# STM32405RG.net
KiCad netlist of a schematic drawn in Altium Designer
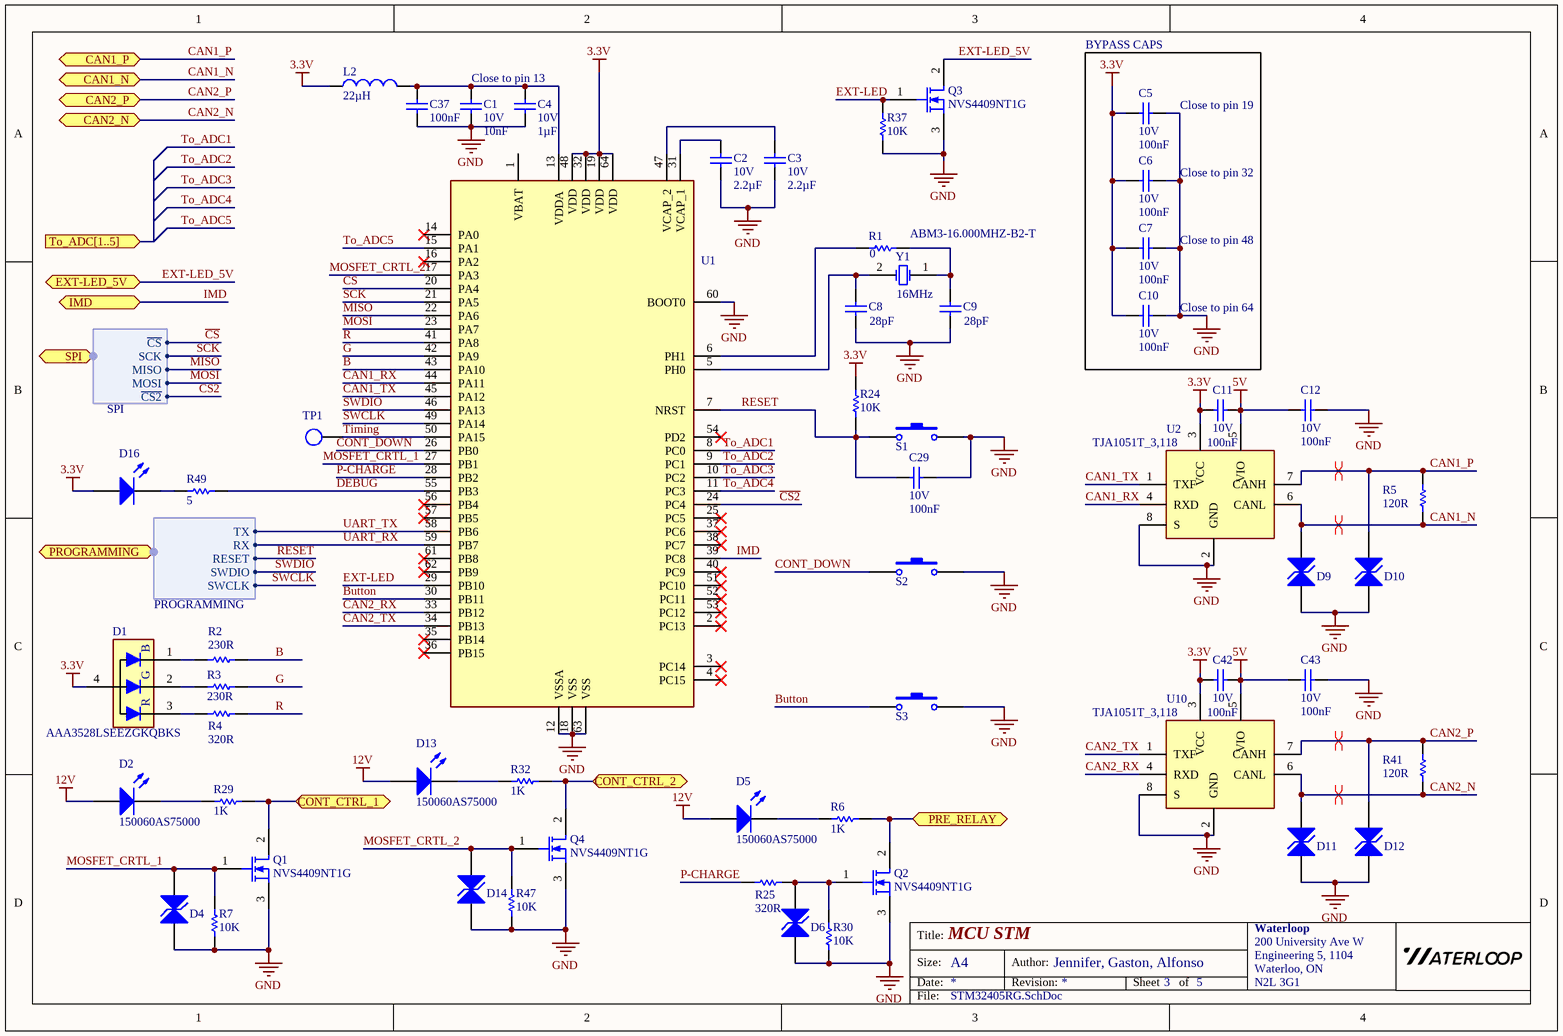
[diagram p0: STM32405RG.SchDoc]

(export (version "E")
  (design (tool "Eeschema 10.0.6"))
  (components
    (comp (ref "C1")
      (value "10V")
      (footprint "0805 - Capacitor")
      (description "C0805C103K8RAC7800. 10000pF ±10% 10V Ceramic Capacitor X7R 0805 (2012 Metric)")
      (fields (field (name "ALTIUM_VALUE") "10nF"))
      (libsource (lib "General") (part "Capacitor - Nonpolarized"))
    )
    (comp (ref "C2")
      (value "10V")
      (footprint "0805 - Capacitor")
      (description "CC0805KKX7R9BB225. 2.2µF ±10% 50V Ceramic Capacitor X7R 0805 (2012 Metric)")
      (fields (field (name "ALTIUM_VALUE") "2.2µF"))
      (libsource (lib "General") (part "Capacitor - Nonpolarized"))
    )
    (comp (ref "C3")
      (value "10V")
      (footprint "0805 - Capacitor")
      (description "CC0805KKX7R9BB225. 2.2µF ±10% 50V Ceramic Capacitor X7R 0805 (2012 Metric)")
      (fields (field (name "ALTIUM_VALUE") "2.2µF"))
      (libsource (lib "General") (part "Capacitor - Nonpolarized"))
    )
    (comp (ref "C4")
      (value "10V")
      (footprint "0805 - Capacitor")
      (description "CL21B105KPFNNNE. 1µF ±10% 10V Ceramic Capacitor X7R 0805 (2012 Metric)")
      (fields (field (name "ALTIUM_VALUE") "1µF"))
      (libsource (lib "General") (part "Capacitor - Nonpolarized"))
    )
    (comp (ref "C5")
      (value "10V")
      (footprint "0805 - Capacitor")
      (description "C0805C104K8RACTU. 0.1µF ±10% 10V Ceramic Capacitor X7R 0805 (2012 Metric)")
      (fields (field (name "ALTIUM_VALUE") "100nF"))
      (libsource (lib "General") (part "Capacitor - Nonpolarized"))
    )
    (comp (ref "C6")
      (value "10V")
      (footprint "0805 - Capacitor")
      (description "C0805C104K8RACTU. 0.1µF ±10% 10V Ceramic Capacitor X7R 0805 (2012 Metric)")
      (fields (field (name "ALTIUM_VALUE") "100nF"))
      (libsource (lib "General") (part "Capacitor - Nonpolarized"))
    )
    (comp (ref "C7")
      (value "10V")
      (footprint "0805 - Capacitor")
      (description "C0805C104K8RACTU. 0.1µF ±10% 10V Ceramic Capacitor X7R 0805 (2012 Metric)")
      (fields (field (name "ALTIUM_VALUE") "100nF"))
      (libsource (lib "General") (part "Capacitor - Nonpolarized"))
    )
    (comp (ref "C8")
      (value "28pF")
      (footprint "0805 - Capacitor")
      (description "CBR08C409B5GAC. 4pF ±0.1pF 50V Ceramic Capacitor C0G, NP0 0805 (2012 Metric)")
      (fields (field (name "Comment") "50V"))
      (libsource (lib "General") (part "Capacitor - Nonpolarized"))
    )
    (comp (ref "C9")
      (value "28pF")
      (footprint "0805 - Capacitor")
      (description "CBR08C409B5GAC. 4pF ±0.1pF 50V Ceramic Capacitor C0G, NP0 0805 (2012 Metric)")
      (fields (field (name "Comment") "50V"))
      (libsource (lib "General") (part "Capacitor - Nonpolarized"))
    )
    (comp (ref "C10")
      (value "10V")
      (footprint "0805 - Capacitor")
      (description "C0805C104K8RACTU. 0.1µF ±10% 10V Ceramic Capacitor X7R 0805 (2012 Metric)")
      (fields (field (name "ALTIUM_VALUE") "100nF"))
      (libsource (lib "General") (part "Capacitor - Nonpolarized"))
    )
    (comp (ref "C11")
      (value "10V")
      (footprint "0805 - Capacitor")
      (description "C0805C104K8RACTU. 0.1µF ±10% 10V Ceramic Capacitor X7R 0805 (2012 Metric)")
      (fields (field (name "ALTIUM_VALUE") "100nF"))
      (libsource (lib "") (part "Capacitor - Nonpolarized_1"))
    )
    (comp (ref "C12")
      (value "10V")
      (footprint "0805 - Capacitor")
      (description "C0805C104K8RACTU. 0.1µF ±10% 10V Ceramic Capacitor X7R 0805 (2012 Metric)")
      (fields (field (name "ALTIUM_VALUE") "100nF"))
      (libsource (lib "General") (part "Capacitor - Nonpolarized"))
    )
    (comp (ref "C29")
      (value "10V")
      (footprint "0805 - Capacitor")
      (description "C0805C104K8RACTU. 0.1µF ±10% 10V Ceramic Capacitor X7R 0805 (2012 Metric)")
      (fields (field (name "ALTIUM_VALUE") "100nF"))
      (libsource (lib "General") (part "Capacitor - Nonpolarized"))
    )
    (comp (ref "C37")
      (value "100nF")
      (footprint "0805 - Capacitor")
      (description "C0805C104K8RACTU. 0.1µF ±10% 10V Ceramic Capacitor X7R 0805 (2012 Metric)")
      (fields (field (name "Comment") "Capacitor - Nonpolarized"))
      (libsource (lib "General") (part "Capacitor - Nonpolarized"))
    )
    (comp (ref "C42")
      (value "10V")
      (footprint "0805 - Capacitor")
      (description "C0805C104K8RACTU. 0.1µF ±10% 10V Ceramic Capacitor X7R 0805 (2012 Metric)")
      (fields (field (name "ALTIUM_VALUE") "100nF"))
      (libsource (lib "") (part "Capacitor - Nonpolarized_1"))
    )
    (comp (ref "C43")
      (value "10V")
      (footprint "0805 - Capacitor")
      (description "C0805C104K8RACTU. 0.1µF ±10% 10V Ceramic Capacitor X7R 0805 (2012 Metric)")
      (fields (field (name "ALTIUM_VALUE") "100nF"))
      (libsource (lib "General") (part "Capacitor - Nonpolarized"))
    )
    (comp (ref "D1")
      (value "AAA3528LSEEZGKQBKS")
      (footprint "4-PLCC RGB LED")
      (libsource (lib "General") (part "RGB LED- Common Anode"))
    )
    (comp (ref "D2")
      (value "150060AS75000")
      (footprint "0603 - Resistor")
      (description "Amber 605nm LED Indication - Discrete 2V 0603 (1608 Metric)")
      (libsource (lib "General") (part "LED"))
    )
    (comp (ref "D4")
      (value "TVS")
      (footprint "SOD123 - DIODE")
      (description "TV02W5V0B-G, TVS DIODE 5VWM 9.2VC SOD123")
      (libsource (lib "General") (part "TVS"))
    )
    (comp (ref "D5")
      (value "150060AS75000")
      (footprint "0603 - Resistor")
      (description "Amber 605nm LED Indication - Discrete 2V 0603 (1608 Metric)")
      (libsource (lib "General") (part "LED"))
    )
    (comp (ref "D6")
      (value "TVS")
      (footprint "SOD123 - DIODE")
      (description "TV02W5V0B-G, TVS DIODE 5VWM 9.2VC SOD123")
      (libsource (lib "General") (part "TVS"))
    )
    (comp (ref "D9")
      (value "TVS")
      (footprint "SOD123 - DIODE")
      (description "TV02W5V0B-G, TVS DIODE 5VWM 9.2VC SOD123")
      (libsource (lib "General") (part "TVS"))
    )
    (comp (ref "D10")
      (value "TVS")
      (footprint "SOD123 - DIODE")
      (description "TV02W5V0B-G, TVS DIODE 5VWM 9.2VC SOD123")
      (libsource (lib "General") (part "TVS"))
    )
    (comp (ref "D11")
      (value "TVS")
      (footprint "SOD123 - DIODE")
      (description "TV02W5V0B-G, TVS DIODE 5VWM 9.2VC SOD123")
      (libsource (lib "General") (part "TVS"))
    )
    (comp (ref "D12")
      (value "TVS")
      (footprint "SOD123 - DIODE")
      (description "TV02W5V0B-G, TVS DIODE 5VWM 9.2VC SOD123")
      (libsource (lib "General") (part "TVS"))
    )
    (comp (ref "D13")
      (value "150060AS75000")
      (footprint "0603 - Resistor")
      (description "Amber 605nm LED Indication - Discrete 2V 0603 (1608 Metric)")
      (libsource (lib "General") (part "LED"))
    )
    (comp (ref "D14")
      (value "TVS")
      (footprint "SOD123 - DIODE")
      (description "TV02W5V0B-G, TVS DIODE 5VWM 9.2VC SOD123")
      (libsource (lib "General") (part "TVS"))
    )
    (comp (ref "D16")
      (value "LED")
      (footprint "0805 - Resistor")
      (description "150080BS75000, LED BLUE CLEAR 0805 SMD")
      (libsource (lib "General") (part "LED"))
    )
    (comp (ref "L2")
      (value "22µH")
      (footprint "0805 - Capacitor")
      (description "LBR2012T220K, 22 µH ±10% 100 mA 0805 (2012 Metric)")
      (fields (field (name "Comment") "Inductor"))
      (libsource (lib "General") (part "Inductor"))
    )
    (comp (ref "Q1")
      (value "NVS4409NT1G")
      (footprint "SC70/SOT323")
      (description "N-Channel MOSFET")
      (libsource (lib "General") (part "MOSFET-N"))
    )
    (comp (ref "Q2")
      (value "NVS4409NT1G")
      (footprint "SC70/SOT323")
      (description "N-Channel MOSFET")
      (libsource (lib "General") (part "MOSFET-N"))
    )
    (comp (ref "Q3")
      (value "NVS4409NT1G")
      (footprint "SC70/SOT323")
      (description "N-Channel MOSFET")
      (libsource (lib "General") (part "MOSFET-N"))
    )
    (comp (ref "Q4")
      (value "NVS4409NT1G")
      (footprint "SC70/SOT323")
      (description "N-Channel MOSFET")
      (libsource (lib "General") (part "MOSFET-N"))
    )
    (comp (ref "R1")
      (value "0")
      (footprint "0603 - Resistor")
      (fields (field (name "Comment") "0603"))
      (libsource (lib "General") (part "Resistor"))
    )
    (comp (ref "R2")
      (value "230R")
      (footprint "0603 - Resistor")
      (fields (field (name "Comment") "1%"))
      (libsource (lib "General") (part "Resistor"))
    )
    (comp (ref "R3")
      (value "230R")
      (footprint "0603 - Resistor")
      (fields (field (name "Comment") "1%"))
      (libsource (lib "General") (part "Resistor"))
    )
    (comp (ref "R4")
      (value "320R")
      (footprint "0603 - Resistor")
      (fields (field (name "Comment") "1%"))
      (libsource (lib "General") (part "Resistor"))
    )
    (comp (ref "R5")
      (value "120R")
      (footprint "0603 - Resistor")
      (fields (field (name "Comment") "1%"))
      (libsource (lib "General") (part "Resistor"))
    )
    (comp (ref "R6")
      (value "1K")
      (footprint "0603 - Resistor")
      (fields (field (name "Comment") "5%"))
      (libsource (lib "General") (part "Resistor"))
    )
    (comp (ref "R7")
      (value "10K")
      (footprint "0603 - Resistor")
      (fields (field (name "Comment") "5%"))
      (libsource (lib "General") (part "Resistor"))
    )
    (comp (ref "R24")
      (value "10K")
      (footprint "0603 - Resistor")
      (fields (field (name "Comment") "5%"))
      (libsource (lib "General") (part "Resistor"))
    )
    (comp (ref "R25")
      (value "320R")
      (footprint "0603 - Resistor")
      (fields (field (name "Comment") "1%"))
      (libsource (lib "General") (part "Resistor"))
    )
    (comp (ref "R29")
      (value "1K")
      (footprint "0603 - Resistor")
      (fields (field (name "Comment") "5%"))
      (libsource (lib "General") (part "Resistor"))
    )
    (comp (ref "R30")
      (value "10K")
      (footprint "0603 - Resistor")
      (fields (field (name "Comment") "5%"))
      (libsource (lib "General") (part "Resistor"))
    )
    (comp (ref "R32")
      (value "1K")
      (footprint "0603 - Resistor")
      (fields (field (name "Comment") "5%"))
      (libsource (lib "General") (part "Resistor"))
    )
    (comp (ref "R37")
      (value "10K")
      (footprint "0603 - Resistor")
      (fields (field (name "Comment") "5%"))
      (libsource (lib "General") (part "Resistor"))
    )
    (comp (ref "R41")
      (value "120R")
      (footprint "0603 - Resistor")
      (fields (field (name "Comment") "1%"))
      (libsource (lib "General") (part "Resistor"))
    )
    (comp (ref "R47")
      (value "10K")
      (footprint "0603 - Resistor")
      (fields (field (name "Comment") "5%"))
      (libsource (lib "General") (part "Resistor"))
    )
    (comp (ref "R49")
      (value "5")
      (footprint "0603 - Resistor")
      (description "RC0603FR-075R1L, RES 5.1 OHM 1% 1/10W 0603")
      (fields (field (name "Comment") "Resistor"))
      (libsource (lib "General") (part "Resistor"))
    )
    (comp (ref "S1")
      (value "PTS636 SM43 SMTR LFS")
      (footprint "6x6mm Switch")
      (description "Tactile Switch SPST-NO Top Actuated Surface Mount")
      (libsource (lib "General") (part "Switch - Push Button"))
    )
    (comp (ref "S2")
      (value "PTS636 SM43 SMTR LFS")
      (footprint "6x6mm Switch")
      (description "Tactile Switch SPST-NO Top Actuated Surface Mount")
      (libsource (lib "General") (part "Switch - Push Button"))
    )
    (comp (ref "S3")
      (value "PTS636 SM43 SMTR LFS")
      (footprint "6x6mm Switch")
      (description "Tactile Switch SPST-NO Top Actuated Surface Mount")
      (libsource (lib "General") (part "Switch - Push Button"))
    )
    (comp (ref "TP1")
      (value "~")
      (footprint "Test Point - 5002")
      (description "Test Point")
      (libsource (lib "General") (part "Test Point"))
    )
    (comp (ref "U1")
      (value "~")
      (footprint "STM32F405RGT6TR")
      (description "ST 64-pin Micro")
      (fields (field (name "MANUFACTURER PART NUMBER") "STM32F405RG") (field (name "MANUFACTURER") "ST"))
      (libsource (lib "GeneralComponents") (part "STM32F405RGT6"))
    )
    (comp (ref "U2")
      (value "TJA1051T_3,118")
      (footprint "TJA1051T/3,118")
      (description "CAN Transceiver IC 4.5V-5.5V 250ns")
      (fields (field (name "MANUFACTURER") "NXP") (field (name "MANUFACTURER PART NUMBER") "TJA1051T/3,118"))
      (libsource (lib "GeneralComponents") (part "TJA1051T_3,118"))
    )
    (comp (ref "U10")
      (value "TJA1051T_3,118")
      (footprint "TJA1051T/3,118")
      (description "CAN Transceiver IC 4.5V-5.5V 250ns")
      (fields (field (name "MANUFACTURER") "NXP") (field (name "MANUFACTURER PART NUMBER") "TJA1051T/3,118"))
      (libsource (lib "GeneralComponents") (part "TJA1051T_3,118"))
    )
    (comp (ref "Y1")
      (value "ABM3-16.000MHZ-B2-T")
      (footprint "2-SMD NO LEAD CRSYSTAL")
      (description "8MHz ±20ppm Crystal 12pF 300 Ohms 2-SMD, No Lead")
      (fields (field (name "ALTIUM_VALUE") "16MHz"))
      (libsource (lib "General") (part "Oscillator"))
    )
  )
  (nets
    (net (code "3") (name "/B") (class "Default")
      (node (ref "R2") (pin "1") (pinfunction "1_1") (pintype "passive"))
      (node (ref "U1") (pin "43") (pinfunction "PA10_43") (pintype "passive"))
    )
    (net (code "4") (name "/Button") (class "Default")
      (node (ref "S3") (pin "1") (pinfunction "1_1") (pintype "passive"))
      (node (ref "U1") (pin "30") (pinfunction "PB11_30") (pintype "passive"))
    )
    (net (code "5") (name "/CAN1_N") (class "Default")
      (node (ref "D9") (pin "2") (pinfunction "K_2") (pintype "passive"))
      (node (ref "R5") (pin "1") (pinfunction "1_1") (pintype "passive"))
      (node (ref "U2") (pin "6") (pinfunction "CANL_6") (pintype "passive"))
    )
    (net (code "6") (name "/CAN1_P") (class "Default")
      (node (ref "D10") (pin "2") (pinfunction "K_2") (pintype "passive"))
      (node (ref "R5") (pin "2") (pinfunction "2_2") (pintype "passive"))
      (node (ref "U2") (pin "7") (pinfunction "CANH_7") (pintype "passive"))
    )
    (net (code "7") (name "/CAN1_RX") (class "Default")
      (node (ref "U1") (pin "44") (pinfunction "PA11_44") (pintype "passive"))
      (node (ref "U2") (pin "4") (pinfunction "RXD_4") (pintype "passive"))
    )
    (net (code "8") (name "/CAN1_TX") (class "Default")
      (node (ref "U1") (pin "45") (pinfunction "PA12_45") (pintype "passive"))
      (node (ref "U2") (pin "1") (pinfunction "TXF_1") (pintype "passive"))
    )
    (net (code "9") (name "/CAN2_N") (class "Default")
      (node (ref "D11") (pin "2") (pinfunction "K_2") (pintype "passive"))
      (node (ref "R41") (pin "1") (pinfunction "1_1") (pintype "passive"))
      (node (ref "U10") (pin "6") (pinfunction "CANL_6") (pintype "passive"))
    )
    (net (code "10") (name "/CAN2_P") (class "Default")
      (node (ref "D12") (pin "2") (pinfunction "K_2") (pintype "passive"))
      (node (ref "R41") (pin "2") (pinfunction "2_2") (pintype "passive"))
      (node (ref "U10") (pin "7") (pinfunction "CANH_7") (pintype "passive"))
    )
    (net (code "11") (name "/CAN2_RX") (class "Default")
      (node (ref "U1") (pin "33") (pinfunction "PB12_33") (pintype "passive"))
      (node (ref "U10") (pin "4") (pinfunction "RXD_4") (pintype "passive"))
    )
    (net (code "12") (name "/CAN2_TX") (class "Default")
      (node (ref "U1") (pin "34") (pinfunction "PB13_34") (pintype "passive"))
      (node (ref "U10") (pin "1") (pinfunction "TXF_1") (pintype "passive"))
    )
    (net (code "13") (name "/CONT_CTRL_1") (class "Default")
      (node (ref "Q1") (pin "2") (pinfunction "D_2") (pintype "passive"))
      (node (ref "R29") (pin "1") (pinfunction "1_1") (pintype "passive"))
    )
    (net (code "14") (name "/CONT_CTRL_2") (class "Default")
      (node (ref "Q4") (pin "2") (pinfunction "D_2") (pintype "passive"))
      (node (ref "R32") (pin "1") (pinfunction "1_1") (pintype "passive"))
    )
    (net (code "15") (name "/CONT_DOWN") (class "Default")
      (node (ref "S2") (pin "1") (pinfunction "1_1") (pintype "passive"))
      (node (ref "U1") (pin "26") (pinfunction "PB0_26") (pintype "passive"))
    )
    (net (code "16") (name "/DEBUG") (class "Default")
      (node (ref "R49") (pin "2") (pinfunction "2_2") (pintype "passive"))
      (node (ref "U1") (pin "55") (pinfunction "PB3_55") (pintype "passive"))
    )
    (net (code "17") (name "/EXT-LED") (class "Default")
      (node (ref "Q3") (pin "1") (pinfunction "G_1") (pintype "passive"))
      (node (ref "R37") (pin "2") (pinfunction "2_2") (pintype "passive"))
      (node (ref "U1") (pin "29") (pinfunction "PB10_29") (pintype "passive"))
    )
    (net (code "18") (name "/EXT-LED_5V") (class "Default")
      (node (ref "Q3") (pin "2") (pinfunction "D_2") (pintype "passive"))
    )
    (net (code "19") (name "/G") (class "Default")
      (node (ref "R3") (pin "1") (pinfunction "1_1") (pintype "passive"))
      (node (ref "U1") (pin "42") (pinfunction "PA9_42") (pintype "passive"))
    )
    (net (code "20") (name "/IMD") (class "Default")
      (node (ref "U1") (pin "39") (pinfunction "PC8_39") (pintype "passive"))
    )
    (net (code "21") (name "/MISO") (class "Default")
      (node (ref "U1") (pin "22") (pinfunction "PA6_22") (pintype "passive"))
    )
    (net (code "22") (name "/MOSFET_CRTL_1") (class "Default")
      (node (ref "D4") (pin "2") (pinfunction "K_2") (pintype "passive"))
      (node (ref "Q1") (pin "1") (pinfunction "G_1") (pintype "passive"))
      (node (ref "R7") (pin "2") (pinfunction "2_2") (pintype "passive"))
      (node (ref "U1") (pin "27") (pinfunction "PB1_27") (pintype "passive"))
    )
    (net (code "23") (name "/MOSFET_CRTL_2") (class "Default")
      (node (ref "D14") (pin "2") (pinfunction "K_2") (pintype "passive"))
      (node (ref "Q4") (pin "1") (pinfunction "G_1") (pintype "passive"))
      (node (ref "R47") (pin "2") (pinfunction "2_2") (pintype "passive"))
      (node (ref "U1") (pin "17") (pinfunction "PA3_17") (pintype "passive"))
    )
    (net (code "24") (name "/MOSI") (class "Default")
      (node (ref "U1") (pin "23") (pinfunction "PA7_23") (pintype "passive"))
    )
    (net (code "25") (name "/P-CHARGE") (class "Default")
      (node (ref "R25") (pin "2") (pinfunction "2_2") (pintype "passive"))
      (node (ref "U1") (pin "28") (pinfunction "PB2_28") (pintype "passive"))
    )
    (net (code "26") (name "/PRE_RELAY") (class "Default")
      (node (ref "Q2") (pin "2") (pinfunction "D_2") (pintype "passive"))
      (node (ref "R6") (pin "1") (pinfunction "1_1") (pintype "passive"))
    )
    (net (code "27") (name "/R") (class "Default")
      (node (ref "R4") (pin "1") (pinfunction "1_1") (pintype "passive"))
      (node (ref "U1") (pin "41") (pinfunction "PA8_41") (pintype "passive"))
    )
    (net (code "28") (name "/RESET") (class "Default")
      (node (ref "C29") (pin "1") (pinfunction "1_1") (pintype "passive"))
      (node (ref "R24") (pin "1") (pinfunction "1_1") (pintype "passive"))
      (node (ref "S1") (pin "1") (pinfunction "1_1") (pintype "passive"))
      (node (ref "U1") (pin "7") (pinfunction "NRST_7") (pintype "passive"))
    )
    (net (code "29") (name "/SCK") (class "Default")
      (node (ref "U1") (pin "21") (pinfunction "PA5_21") (pintype "passive"))
    )
    (net (code "30") (name "/SWCLK") (class "Default")
      (node (ref "U1") (pin "49") (pinfunction "PA14_49") (pintype "passive"))
    )
    (net (code "31") (name "/SWDIO") (class "Default")
      (node (ref "U1") (pin "46") (pinfunction "PA13_46") (pintype "passive"))
    )
    (net (code "32") (name "/Timing") (class "Default")
      (node (ref "TP1") (pin "1") (pinfunction "0_1") (pintype "passive"))
      (node (ref "U1") (pin "50") (pinfunction "PA15_50") (pintype "passive"))
    )
    (net (code "33") (name "/To_ADC1") (class "Default")
      (node (ref "U1") (pin "8") (pinfunction "PC0_8") (pintype "passive"))
    )
    (net (code "34") (name "/To_ADC2") (class "Default")
      (node (ref "U1") (pin "9") (pinfunction "PC1_9") (pintype "passive"))
    )
    (net (code "35") (name "/To_ADC3") (class "Default")
      (node (ref "U1") (pin "10") (pinfunction "PC2_10") (pintype "passive"))
    )
    (net (code "36") (name "/To_ADC4") (class "Default")
      (node (ref "U1") (pin "11") (pinfunction "PC3_11") (pintype "passive"))
    )
    (net (code "37") (name "/To_ADC5") (class "Default")
      (node (ref "U1") (pin "15") (pinfunction "PA1_15") (pintype "passive"))
    )
    (net (code "39") (name "/UART_RX") (class "Default")
      (node (ref "U1") (pin "59") (pinfunction "PB7_59") (pintype "passive"))
    )
    (net (code "40") (name "/UART_TX") (class "Default")
      (node (ref "U1") (pin "58") (pinfunction "PB6_58") (pintype "passive"))
    )
    (net (code "43") (name "/~{CS2}") (class "Default")
      (node (ref "U1") (pin "24") (pinfunction "PC4_24") (pintype "passive"))
    )
    (net (code "44") (name "/~{CS}") (class "Default")
      (node (ref "U1") (pin "20") (pinfunction "PA4_20") (pintype "passive"))
    )
    (net (code "45") (name "3.3V") (class "Default")
      (node (ref "C10") (pin "1") (pinfunction "1_1") (pintype "passive"))
      (node (ref "C11") (pin "2") (pinfunction "2_2") (pintype "passive"))
      (node (ref "C42") (pin "2") (pinfunction "2_2") (pintype "passive"))
      (node (ref "C5") (pin "1") (pinfunction "1_1") (pintype "passive"))
      (node (ref "C6") (pin "1") (pinfunction "1_1") (pintype "passive"))
      (node (ref "C7") (pin "1") (pinfunction "1_1") (pintype "passive"))
      (node (ref "D1") (pin "4") (pinfunction "11_4") (pintype "passive"))
      (node (ref "D16") (pin "1") (pinfunction "A_1") (pintype "passive"))
      (node (ref "L2") (pin "1") (pinfunction "1_1") (pintype "passive"))
      (node (ref "R24") (pin "2") (pinfunction "2_2") (pintype "passive"))
      (node (ref "U1") (pin "19") (pinfunction "VDD_19") (pintype "power_in"))
      (node (ref "U1") (pin "32") (pinfunction "VDD_32") (pintype "power_in"))
      (node (ref "U1") (pin "48") (pinfunction "VDD_48") (pintype "power_in"))
      (node (ref "U1") (pin "64") (pinfunction "VDD_64") (pintype "power_in"))
      (node (ref "U10") (pin "3") (pinfunction "VCC_3") (pintype "passive"))
      (node (ref "U2") (pin "3") (pinfunction "VCC_3") (pintype "passive"))
    )
    (net (code "46") (name "5V") (class "Default")
      (node (ref "C11") (pin "1") (pinfunction "1_1") (pintype "passive"))
      (node (ref "C12") (pin "1") (pinfunction "1_1") (pintype "passive"))
      (node (ref "C42") (pin "1") (pinfunction "1_1") (pintype "passive"))
      (node (ref "C43") (pin "1") (pinfunction "1_1") (pintype "passive"))
      (node (ref "U10") (pin "5") (pinfunction "VIO_5") (pintype "passive"))
      (node (ref "U2") (pin "5") (pinfunction "VIO_5") (pintype "passive"))
    )
    (net (code "47") (name "12V") (class "Default")
      (node (ref "D13") (pin "1") (pinfunction "A_1") (pintype "passive"))
      (node (ref "D2") (pin "1") (pinfunction "A_1") (pintype "passive"))
      (node (ref "D5") (pin "1") (pinfunction "A_1") (pintype "passive"))
    )
    (net (code "48") (name "GND") (class "Default")
      (node (ref "C1") (pin "1") (pinfunction "1_1") (pintype "passive"))
      (node (ref "C10") (pin "2") (pinfunction "2_2") (pintype "passive"))
      (node (ref "C12") (pin "2") (pinfunction "2_2") (pintype "passive"))
      (node (ref "C2") (pin "1") (pinfunction "1_1") (pintype "passive"))
      (node (ref "C29") (pin "2") (pinfunction "2_2") (pintype "passive"))
      (node (ref "C3") (pin "1") (pinfunction "1_1") (pintype "passive"))
      (node (ref "C37") (pin "1") (pinfunction "1_1") (pintype "passive"))
      (node (ref "C4") (pin "2") (pinfunction "2_2") (pintype "passive"))
      (node (ref "C43") (pin "2") (pinfunction "2_2") (pintype "passive"))
      (node (ref "C5") (pin "2") (pinfunction "2_2") (pintype "passive"))
      (node (ref "C6") (pin "2") (pinfunction "2_2") (pintype "passive"))
      (node (ref "C7") (pin "2") (pinfunction "2_2") (pintype "passive"))
      (node (ref "C8") (pin "1") (pinfunction "1_1") (pintype "passive"))
      (node (ref "C9") (pin "1") (pinfunction "1_1") (pintype "passive"))
      (node (ref "D10") (pin "1") (pinfunction "A_1") (pintype "passive"))
      (node (ref "D11") (pin "1") (pinfunction "A_1") (pintype "passive"))
      (node (ref "D12") (pin "1") (pinfunction "A_1") (pintype "passive"))
      (node (ref "D14") (pin "1") (pinfunction "A_1") (pintype "passive"))
      (node (ref "D4") (pin "1") (pinfunction "A_1") (pintype "passive"))
      (node (ref "D6") (pin "1") (pinfunction "A_1") (pintype "passive"))
      (node (ref "D9") (pin "1") (pinfunction "A_1") (pintype "passive"))
      (node (ref "Q1") (pin "3") (pinfunction "S_3") (pintype "passive"))
      (node (ref "Q2") (pin "3") (pinfunction "S_3") (pintype "passive"))
      (node (ref "Q3") (pin "3") (pinfunction "S_3") (pintype "passive"))
      (node (ref "Q4") (pin "3") (pinfunction "S_3") (pintype "passive"))
      (node (ref "R30") (pin "1") (pinfunction "1_1") (pintype "passive"))
      (node (ref "R37") (pin "1") (pinfunction "1_1") (pintype "passive"))
      (node (ref "R47") (pin "1") (pinfunction "1_1") (pintype "passive"))
      (node (ref "R7") (pin "1") (pinfunction "1_1") (pintype "passive"))
      (node (ref "S1") (pin "2") (pinfunction "2_2") (pintype "passive"))
      (node (ref "S2") (pin "2") (pinfunction "2_2") (pintype "passive"))
      (node (ref "S3") (pin "2") (pinfunction "2_2") (pintype "passive"))
      (node (ref "U1") (pin "12") (pinfunction "VSSA_12") (pintype "power_in"))
      (node (ref "U1") (pin "18") (pinfunction "VSS_18") (pintype "power_in"))
      (node (ref "U1") (pin "60") (pinfunction "BOOT0_60") (pintype "passive"))
      (node (ref "U1") (pin "63") (pinfunction "VSS_63") (pintype "power_in"))
      (node (ref "U10") (pin "2") (pinfunction "GND_2") (pintype "passive"))
      (node (ref "U10") (pin "8") (pinfunction "S_8") (pintype "passive"))
      (node (ref "U2") (pin "2") (pinfunction "GND_2") (pintype "passive"))
      (node (ref "U2") (pin "8") (pinfunction "S_8") (pintype "passive"))
    )
    (net (code "49") (name "Net-(D1-11-Pad1)") (class "Default")
      (node (ref "D1") (pin "1") (pinfunction "11_1") (pintype "passive"))
      (node (ref "R2") (pin "2") (pinfunction "2_2") (pintype "passive"))
    )
    (net (code "50") (name "Net-(D1-11-Pad2)") (class "Default")
      (node (ref "D1") (pin "2") (pinfunction "11_2") (pintype "passive"))
      (node (ref "R3") (pin "2") (pinfunction "2_2") (pintype "passive"))
    )
    (net (code "51") (name "Net-(D1-11-Pad3)") (class "Default")
      (node (ref "D1") (pin "3") (pinfunction "11_3") (pintype "passive"))
      (node (ref "R4") (pin "2") (pinfunction "2_2") (pintype "passive"))
    )
    (net (code "52") (name "Net-(D2-K)") (class "Default")
      (node (ref "D2") (pin "2") (pinfunction "K_2") (pintype "passive"))
      (node (ref "R29") (pin "2") (pinfunction "2_2") (pintype "passive"))
    )
    (net (code "53") (name "Net-(D5-K)") (class "Default")
      (node (ref "D5") (pin "2") (pinfunction "K_2") (pintype "passive"))
      (node (ref "R6") (pin "2") (pinfunction "2_2") (pintype "passive"))
    )
    (net (code "54") (name "Net-(D6-K)") (class "Default")
      (node (ref "D6") (pin "2") (pinfunction "K_2") (pintype "passive"))
      (node (ref "Q2") (pin "1") (pinfunction "G_1") (pintype "passive"))
      (node (ref "R25") (pin "1") (pinfunction "1_1") (pintype "passive"))
      (node (ref "R30") (pin "2") (pinfunction "2_2") (pintype "passive"))
    )
    (net (code "55") (name "Net-(D13-K)") (class "Default")
      (node (ref "D13") (pin "2") (pinfunction "K_2") (pintype "passive"))
      (node (ref "R32") (pin "2") (pinfunction "2_2") (pintype "passive"))
    )
    (net (code "56") (name "Net-(D16-K)") (class "Default")
      (node (ref "D16") (pin "2") (pinfunction "K_2") (pintype "passive"))
      (node (ref "R49") (pin "1") (pinfunction "1_1") (pintype "passive"))
    )
    (net (code "57") (name "Net-(U1-PH0)") (class "Default")
      (node (ref "C8") (pin "2") (pinfunction "2_2") (pintype "passive"))
      (node (ref "U1") (pin "5") (pinfunction "PH0_5") (pintype "passive"))
      (node (ref "Y1") (pin "2") (pinfunction "OSC2_2") (pintype "passive"))
    )
    (net (code "58") (name "Net-(U1-PH1)") (class "Default")
      (node (ref "R1") (pin "1") (pinfunction "1_1") (pintype "passive"))
      (node (ref "U1") (pin "6") (pinfunction "PH1_6") (pintype "passive"))
    )
    (net (code "59") (name "Net-(U1-VCAP_1)") (class "Default")
      (node (ref "C2") (pin "2") (pinfunction "2_2") (pintype "passive"))
      (node (ref "U1") (pin "31") (pinfunction "VCAP_1_31") (pintype "power_in"))
    )
    (net (code "60") (name "Net-(U1-VCAP_2)") (class "Default")
      (node (ref "C3") (pin "2") (pinfunction "2_2") (pintype "passive"))
      (node (ref "U1") (pin "47") (pinfunction "VCAP_2_47") (pintype "power_in"))
    )
    (net (code "61") (name "Net-(U1-VDDA)") (class "Default")
      (node (ref "C1") (pin "2") (pinfunction "2_2") (pintype "passive"))
      (node (ref "C37") (pin "2") (pinfunction "2_2") (pintype "passive"))
      (node (ref "C4") (pin "1") (pinfunction "1_1") (pintype "passive"))
      (node (ref "L2") (pin "2") (pinfunction "2_2") (pintype "passive"))
      (node (ref "U1") (pin "13") (pinfunction "VDDA_13") (pintype "power_in"))
    )
    (net (code "62") (name "Net-(Y1-OSC1)") (class "Default")
      (node (ref "C9") (pin "2") (pinfunction "2_2") (pintype "passive"))
      (node (ref "R1") (pin "2") (pinfunction "2_2") (pintype "passive"))
      (node (ref "Y1") (pin "1") (pinfunction "OSC1_1") (pintype "passive"))
    )
    (net (code "63") (name "unconnected-(U1-PA0-Pad14)") (class "Default")
      (node (ref "U1") (pin "14") (pinfunction "PA0_14") (pintype "passive+no_connect"))
    )
    (net (code "64") (name "unconnected-(U1-PA2-Pad16)") (class "Default")
      (node (ref "U1") (pin "16") (pinfunction "PA2_16") (pintype "passive+no_connect"))
    )
    (net (code "65") (name "unconnected-(U1-PB4-Pad56)") (class "Default")
      (node (ref "U1") (pin "56") (pinfunction "PB4_56") (pintype "passive+no_connect"))
    )
    (net (code "66") (name "unconnected-(U1-PB5-Pad57)") (class "Default")
      (node (ref "U1") (pin "57") (pinfunction "PB5_57") (pintype "passive+no_connect"))
    )
    (net (code "67") (name "unconnected-(U1-PB8-Pad61)") (class "Default")
      (node (ref "U1") (pin "61") (pinfunction "PB8_61") (pintype "passive+no_connect"))
    )
    (net (code "68") (name "unconnected-(U1-PB9-Pad62)") (class "Default")
      (node (ref "U1") (pin "62") (pinfunction "PB9_62") (pintype "passive+no_connect"))
    )
    (net (code "69") (name "unconnected-(U1-PB14-Pad35)") (class "Default")
      (node (ref "U1") (pin "35") (pinfunction "PB14_35") (pintype "passive+no_connect"))
    )
    (net (code "70") (name "unconnected-(U1-PB15-Pad36)") (class "Default")
      (node (ref "U1") (pin "36") (pinfunction "PB15_36") (pintype "passive+no_connect"))
    )
    (net (code "71") (name "unconnected-(U1-PC5-Pad25)") (class "Default")
      (node (ref "U1") (pin "25") (pinfunction "PC5_25") (pintype "passive+no_connect"))
    )
    (net (code "72") (name "unconnected-(U1-PC6-Pad37)") (class "Default")
      (node (ref "U1") (pin "37") (pinfunction "PC6_37") (pintype "passive+no_connect"))
    )
    (net (code "73") (name "unconnected-(U1-PC7-Pad38)") (class "Default")
      (node (ref "U1") (pin "38") (pinfunction "PC7_38") (pintype "passive+no_connect"))
    )
    (net (code "74") (name "unconnected-(U1-PC9-Pad40)") (class "Default")
      (node (ref "U1") (pin "40") (pinfunction "PC9_40") (pintype "passive+no_connect"))
    )
    (net (code "75") (name "unconnected-(U1-PC10-Pad51)") (class "Default")
      (node (ref "U1") (pin "51") (pinfunction "PC10_51") (pintype "passive+no_connect"))
    )
    (net (code "76") (name "unconnected-(U1-PC11-Pad52)") (class "Default")
      (node (ref "U1") (pin "52") (pinfunction "PC11_52") (pintype "passive+no_connect"))
    )
    (net (code "77") (name "unconnected-(U1-PC12-Pad53)") (class "Default")
      (node (ref "U1") (pin "53") (pinfunction "PC12_53") (pintype "passive+no_connect"))
    )
    (net (code "78") (name "unconnected-(U1-PC13-Pad2)") (class "Default")
      (node (ref "U1") (pin "2") (pinfunction "PC13_2") (pintype "passive+no_connect"))
    )
    (net (code "79") (name "unconnected-(U1-PC14-Pad3)") (class "Default")
      (node (ref "U1") (pin "3") (pinfunction "PC14_3") (pintype "passive+no_connect"))
    )
    (net (code "80") (name "unconnected-(U1-PC15-Pad4)") (class "Default")
      (node (ref "U1") (pin "4") (pinfunction "PC15_4") (pintype "passive+no_connect"))
    )
    (net (code "81") (name "unconnected-(U1-PD2-Pad54)") (class "Default")
      (node (ref "U1") (pin "54") (pinfunction "PD2_54") (pintype "passive+no_connect"))
    )
    (net (code "82") (name "unconnected-(U1-VBAT-Pad1)") (class "Default")
      (node (ref "U1") (pin "1") (pinfunction "VBAT_1") (pintype "power_in"))
    )
  )
)
